# 11_-_CPU_-_JTAG_CONTROL.net
KiCad netlist of a schematic drawn in Altium Designer
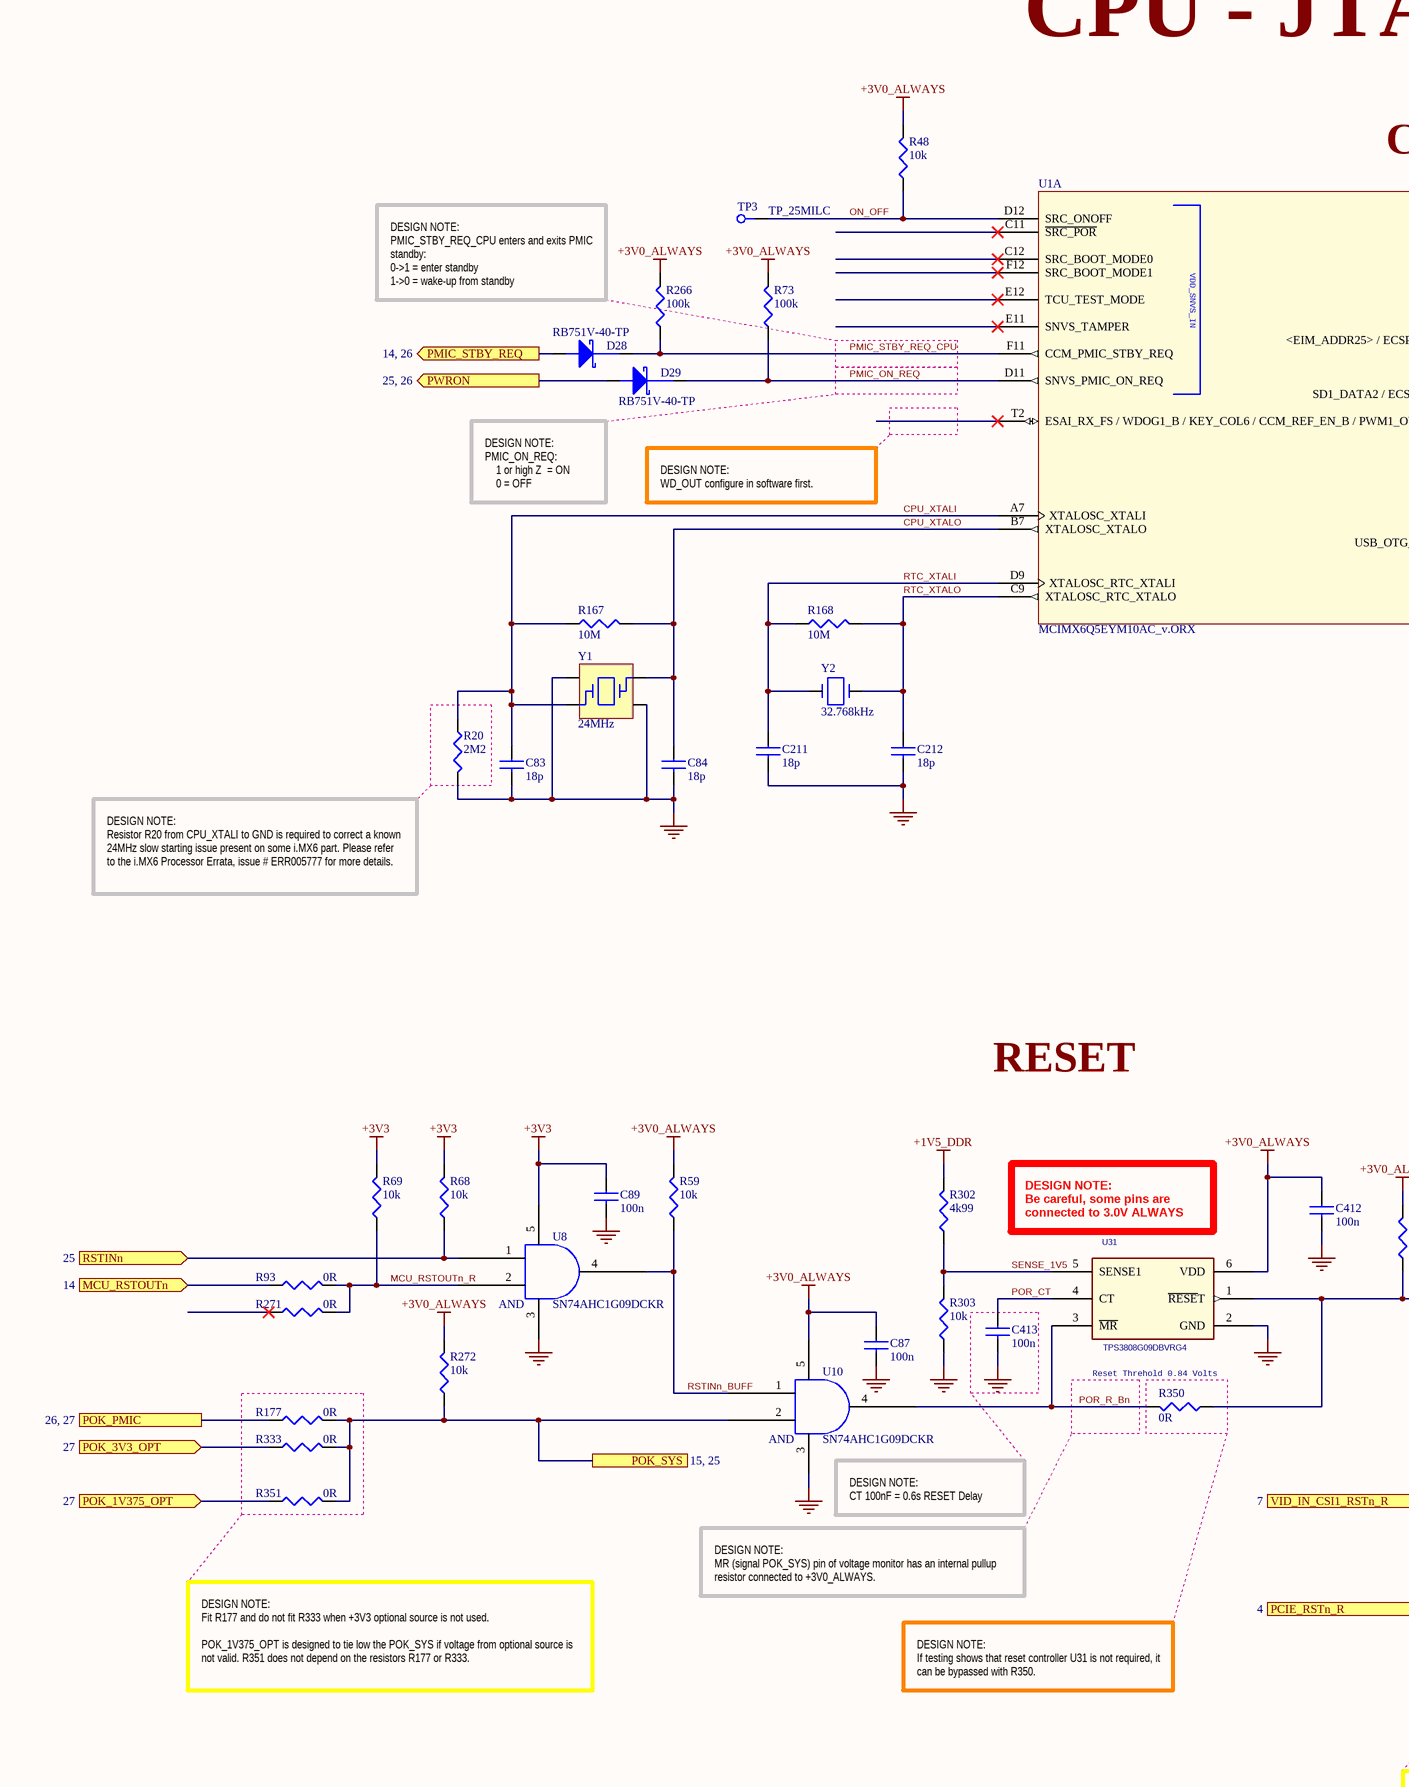
[diagram p0: [11] - CPU - JTAG, CONTROL.SchDoc, left]
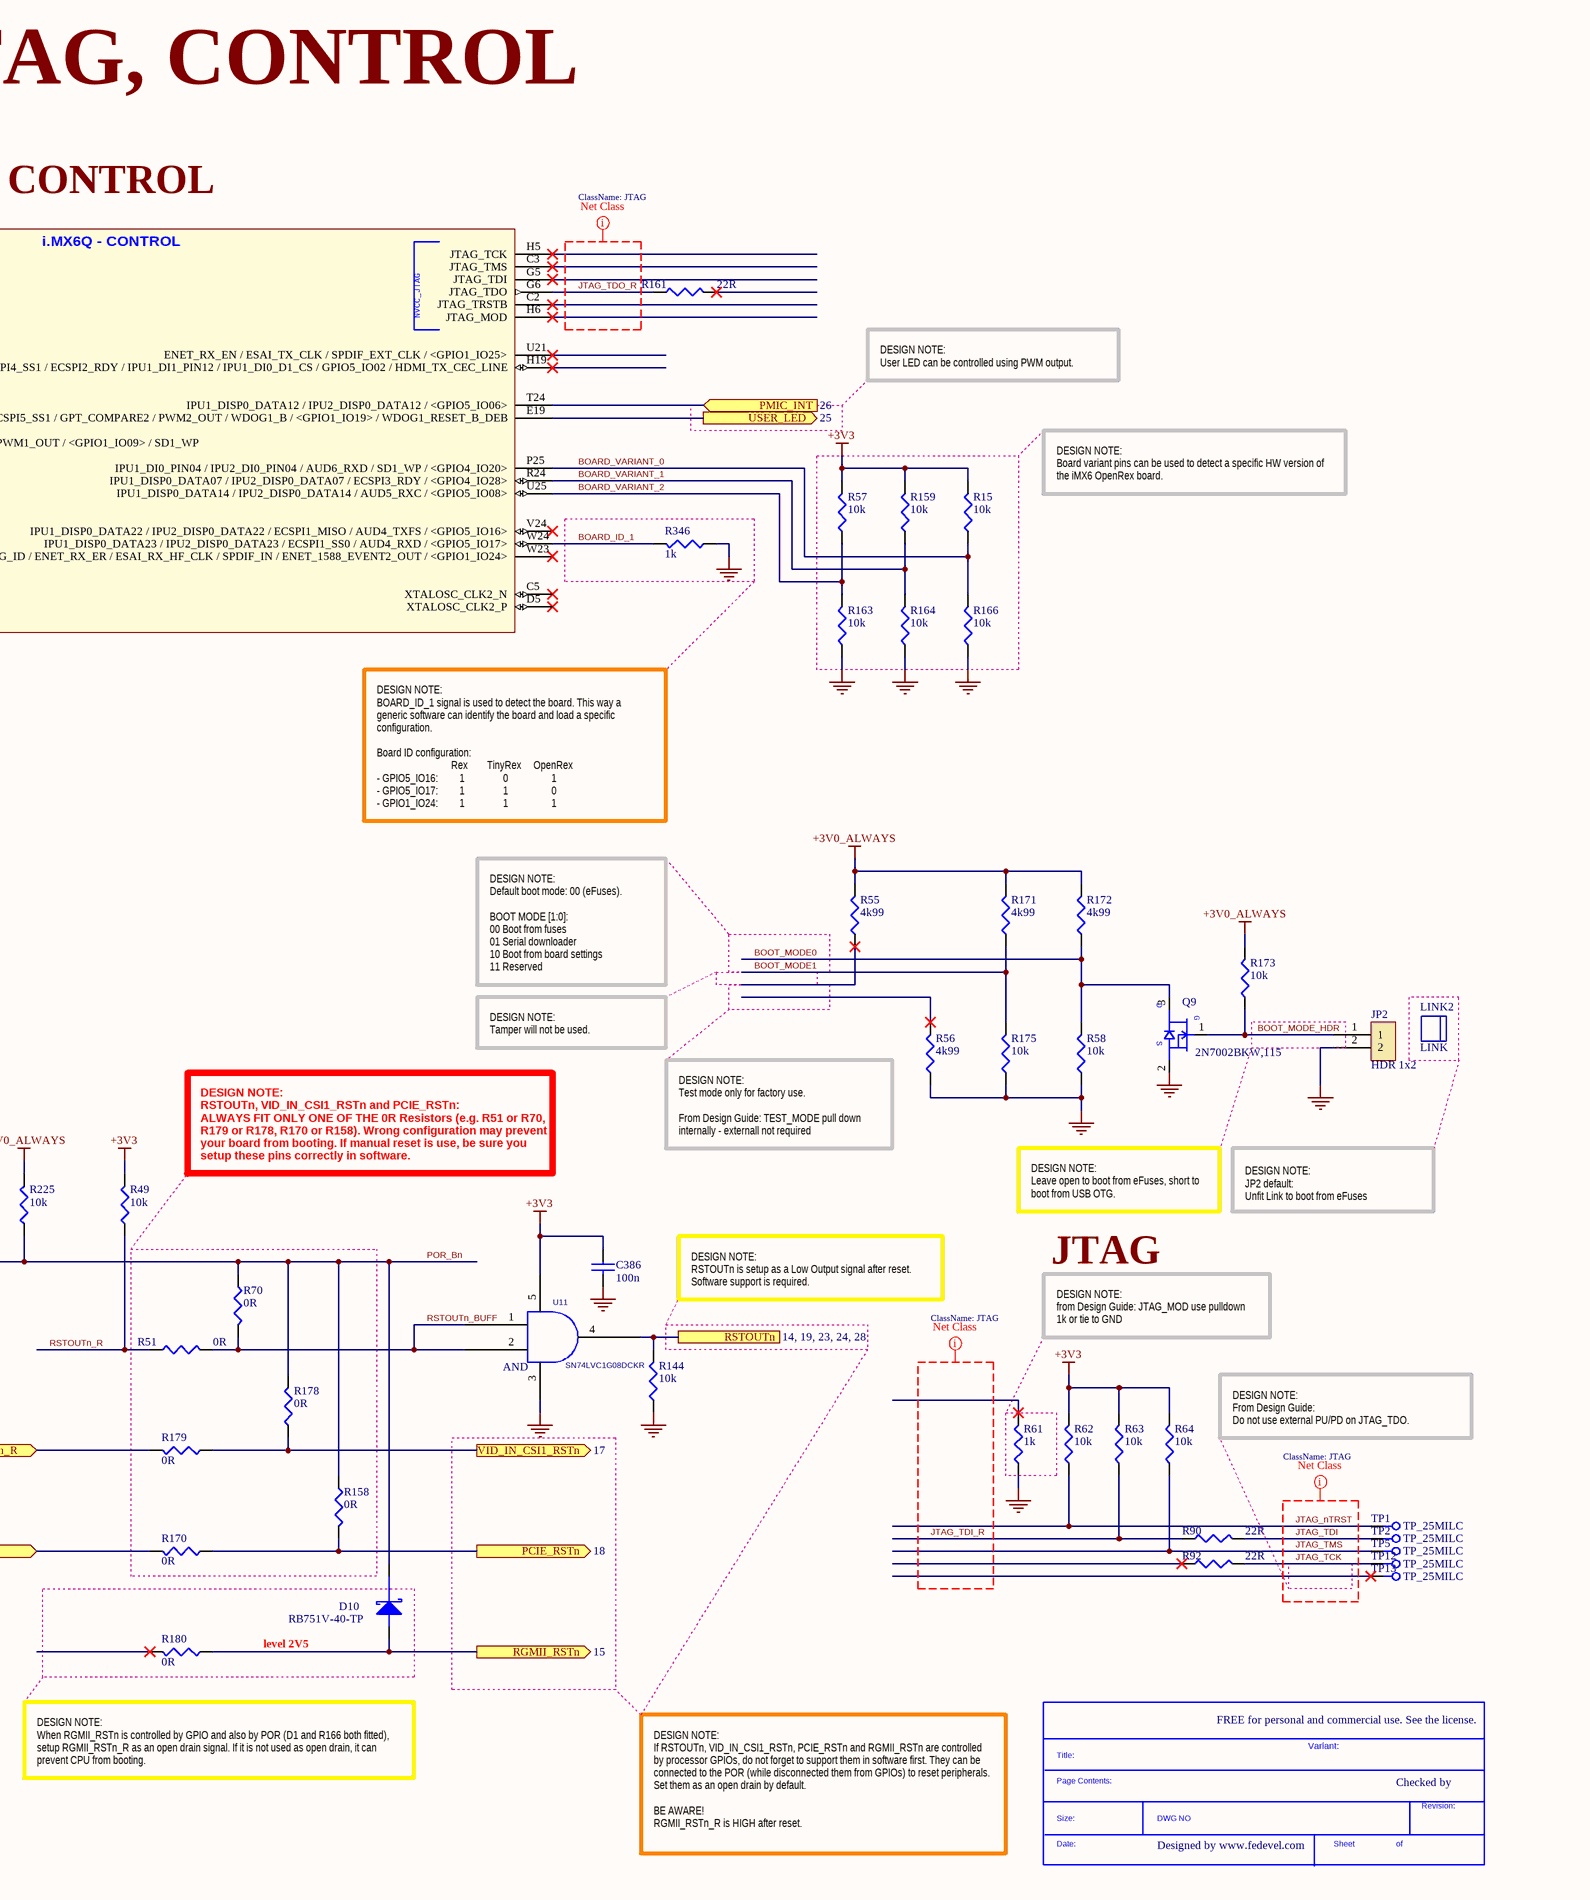
[diagram p1: [11] - CPU - JTAG, CONTROL.SchDoc, right]

(export (version "E")
  (design (tool "Eeschema 10.0.6"))
  (components
    (comp (ref "C83")
      (value "18p")
      (footprint "C0402")
      (description "CAP CER 18PF 50V C0G 5% 0402")
      (fields
        (field (name "MANUFACTURER") "TDK Corporation")
        (field (name "MANUFACTURER PART NUMBER") "C1005C0G1H180J")
      )
      (libsource (lib "Integrated_Library_FEDEVEL_APR_2015") (part "C1005C0G1H180J"))
    )
    (comp (ref "C84")
      (value "18p")
      (footprint "C0402")
      (description "CAP CER 18PF 50V C0G 5% 0402")
      (fields
        (field (name "MANUFACTURER") "TDK Corporation")
        (field (name "MANUFACTURER PART NUMBER") "C1005C0G1H180J")
      )
      (libsource (lib "Integrated_Library_FEDEVEL_APR_2015") (part "C1005C0G1H180J"))
    )
    (comp (ref "C87")
      (value "100n")
      (footprint "C0402")
      (description "CAP CER .10UF 50V X5R 10% 0402")
      (fields
        (field (name "MANUFACTURER") "TDK Corporation")
        (field (name "MANUFACTURER PART NUMBER") "C1005X5R1H104K")
      )
      (libsource (lib "Integrated_Library_FEDEVEL_APR_2015") (part "C1005X5R1H104K"))
    )
    (comp (ref "C89")
      (value "100n")
      (footprint "C0402")
      (description "CAP CER .10UF 50V X5R 10% 0402")
      (fields
        (field (name "MANUFACTURER") "TDK Corporation")
        (field (name "MANUFACTURER PART NUMBER") "C1005X5R1H104K")
      )
      (libsource (lib "Integrated_Library_FEDEVEL_APR_2015") (part "C1005X5R1H104K"))
    )
    (comp (ref "C211")
      (value "18p")
      (footprint "C0201")
      (description "CAP CER 18PF 50V 5% C0G 0201")
      (fields
        (field (name "MANUFACTURER") "TDK Corporation")
        (field (name "MANUFACTURER PART NUMBER") "C0603C0G1H180J030BA")
        (field (name ".CREATOR") "MM")
        (field (name ".CHECKED PCB") "MM")
        (field (name ".CHECKED SCH") "MM")
      )
      (libsource (lib "Integrated_Library_FEDEVEL_0201") (part "C0603C0G1H180J030BA"))
    )
    (comp (ref "C212")
      (value "18p")
      (footprint "C0201")
      (description "CAP CER 18PF 50V 5% C0G 0201")
      (fields
        (field (name "MANUFACTURER") "TDK Corporation")
        (field (name "MANUFACTURER PART NUMBER") "C0603C0G1H180J030BA")
        (field (name ".CREATOR") "MM")
        (field (name ".CHECKED PCB") "MM")
        (field (name ".CHECKED SCH") "MM")
      )
      (libsource (lib "Integrated_Library_FEDEVEL_0201") (part "C0603C0G1H180J030BA"))
    )
    (comp (ref "C386")
      (value "100n")
      (footprint "C0402")
      (description "CAP CER .10UF 50V X5R 10% 0402")
      (fields
        (field (name "MANUFACTURER") "TDK Corporation")
        (field (name "MANUFACTURER PART NUMBER") "C1005X5R1H104K")
      )
      (libsource (lib "Integrated_Library_FEDEVEL_APR_2015") (part "C1005X5R1H104K"))
    )
    (comp (ref "C412")
      (value "100n")
      (footprint "C0402")
      (description "CAP CER .10UF 50V X5R 10% 0402")
      (fields
        (field (name "MANUFACTURER") "TDK Corporation")
        (field (name "MANUFACTURER PART NUMBER") "C1005X5R1H104K")
      )
      (libsource (lib "Integrated_Library_FEDEVEL_APR_2015") (part "C1005X5R1H104K"))
    )
    (comp (ref "C413")
      (value "100n")
      (footprint "C0402")
      (description "CAP CER .10UF 50V X5R 10% 0402")
      (fields
        (field (name "MANUFACTURER") "TDK Corporation")
        (field (name "MANUFACTURER PART NUMBER") "C1005X5R1H104K")
      )
      (libsource (lib "Integrated_Library_FEDEVEL_APR_2015") (part "C1005X5R1H104K"))
    )
    (comp (ref "D10")
      (value "RB751V-40-TP")
      (footprint "SOD323")
      (description "DIODE SCHTKY 30MA 30V SOD-323")
      (fields (field (name "MANUFACTURER") "Micro Commercial Co"))
      (libsource (lib "Integrated_Library_FEDEVEL_APR_2015") (part "RB751V-40-TP"))
    )
    (comp (ref "D28")
      (value "RB751V-40-TP")
      (footprint "SOD323")
      (description "DIODE SCHTKY 30MA 30V SOD-323")
      (fields (field (name "MANUFACTURER") "Micro Commercial Co"))
      (libsource (lib "Integrated_Library_FEDEVEL_APR_2015") (part "RB751V-40-TP"))
    )
    (comp (ref "D29")
      (value "RB751V-40-TP")
      (footprint "SOD323")
      (description "DIODE SCHTKY 30MA 30V SOD-323")
      (fields (field (name "MANUFACTURER") "Micro Commercial Co"))
      (libsource (lib "Integrated_Library_FEDEVEL_APR_2015") (part "RB751V-40-TP"))
    )
    (comp (ref "JP2")
      (value "HDR 1x2")
      (footprint "HDR_1x2_2.54MM")
      (description "BERGSTIK II .100\" SR STRAIGHT")
      (fields (field (name "MANUFACTURER") "FCI") (field (name "MANUFACTURER PART NUMBER") "68001-202HLF"))
      (libsource (lib "Integrated_Library_FEDEVEL_APR_2015") (part "68001-202HLF"))
    )
    (comp (ref "LINK2")
      (value "LINK")
      (description "CONN JUMPER SHORTING .100\" GOLD")
      (fields
        (field (name "MANUFACTURER") "Sullins Connector Solutions")
        (field (name "MANUFACTURER PART NUMBER") "QPC02SXGN-RC")
      )
      (libsource (lib "Integrated_Library_FEDEVEL_APR_2015") (part "QPC02SXGN-RC"))
    )
    (comp (ref "Q9")
      (value "2N7002BKW,115")
      (footprint "SC70_SOT323")
      (description "MOSFET N-CH 60V 310MA SOT323")
      (fields (field (name "MANUFACTURER") "NXP Semiconductors"))
      (libsource (lib "Integrated_Library_FEDEVEL_APR_2015") (part "2N7002BKW,115"))
    )
    (comp (ref "R15")
      (value "10k")
      (footprint "R0402")
      (description "RES 10.0K OHM 1/16W 1% 0402 SMD")
      (fields
        (field (name "MANUFACTURER") "Yageo")
        (field (name "MANUFACTURER PART NUMBER") "RC0402FR-0710KL")
      )
      (libsource (lib "Integrated_Library_FEDEVEL_APR_2015") (part "RC0402FR-0710KL"))
    )
    (comp (ref "R20")
      (value "2M2")
      (footprint "R0402")
      (description "RES 2.20M OHM 1/16W 1% 0402 SMD")
      (fields
        (field (name "MANUFACTURER") "Vishay Dale")
        (field (name "MANUFACTURER PART NUMBER") "CRCW04022M20FKED")
        (field (name ".CREATOR") "MM")
      )
      (libsource (lib "Integrated_Library_FEDEVEL_APR_2015") (part "CRCW04022M20FKED"))
    )
    (comp (ref "R48")
      (value "10k")
      (footprint "R0402")
      (description "RES 10.0K OHM 1/16W 1% 0402 SMD")
      (fields
        (field (name "MANUFACTURER") "Yageo")
        (field (name "MANUFACTURER PART NUMBER") "RC0402FR-0710KL")
      )
      (libsource (lib "Integrated_Library_FEDEVEL_APR_2015") (part "RC0402FR-0710KL"))
    )
    (comp (ref "R49")
      (value "10k")
      (footprint "R0402")
      (description "RES 10.0K OHM 1/16W 1% 0402 SMD")
      (fields
        (field (name "MANUFACTURER") "Yageo")
        (field (name "MANUFACTURER PART NUMBER") "RC0402FR-0710KL")
      )
      (libsource (lib "Integrated_Library_FEDEVEL_APR_2015") (part "RC0402FR-0710KL"))
    )
    (comp (ref "R51")
      (value "0R")
      (footprint "R0402")
      (description "RES 0.0 OHM 1/16W 0402 SMD")
      (fields
        (field (name "MANUFACTURER") "Yageo")
        (field (name "MANUFACTURER PART NUMBER") "RC0402JR-070RL")
      )
      (libsource (lib "Integrated_Library_FEDEVEL_APR_2015") (part "RC0402JR-070RL"))
    )
    (comp (ref "R55")
      (value "4k99")
      (footprint "R0201")
      (description "RES 4.99K OHM 1/20W 1% 0201")
      (fields
        (field (name "MANUFACTURER") "Stackpole Electronics Inc")
        (field (name "MANUFACTURER PART NUMBER") "RMCF0201FT4K99")
        (field (name ".CREATOR") "MM")
        (field (name ".CHECKED PCB") "MM")
        (field (name ".CHECKED SCH") "MM")
      )
      (libsource (lib "Integrated_Library_FEDEVEL_0201") (part "RMCF0201FT4K99"))
    )
    (comp (ref "R56")
      (value "4k99")
      (footprint "R0201")
      (description "RES 4.99K OHM 1/20W 1% 0201")
      (fields
        (field (name "MANUFACTURER") "Stackpole Electronics Inc")
        (field (name "MANUFACTURER PART NUMBER") "RMCF0201FT4K99")
        (field (name ".CREATOR") "MM")
        (field (name ".CHECKED PCB") "MM")
        (field (name ".CHECKED SCH") "MM")
      )
      (libsource (lib "Integrated_Library_FEDEVEL_0201") (part "RMCF0201FT4K99"))
    )
    (comp (ref "R57")
      (value "10k")
      (footprint "R0402")
      (description "RES 10.0K OHM 1/16W 1% 0402 SMD")
      (fields
        (field (name "MANUFACTURER") "Yageo")
        (field (name "MANUFACTURER PART NUMBER") "RC0402FR-0710KL")
      )
      (libsource (lib "Integrated_Library_FEDEVEL_APR_2015") (part "RC0402FR-0710KL"))
    )
    (comp (ref "R58")
      (value "10k")
      (footprint "R0402")
      (description "RES 10.0K OHM 1/16W 1% 0402 SMD")
      (fields
        (field (name "MANUFACTURER") "Yageo")
        (field (name "MANUFACTURER PART NUMBER") "RC0402FR-0710KL")
      )
      (libsource (lib "Integrated_Library_FEDEVEL_APR_2015") (part "RC0402FR-0710KL"))
    )
    (comp (ref "R59")
      (value "10k")
      (footprint "R0402")
      (description "RES 10.0K OHM 1/16W 1% 0402 SMD")
      (fields
        (field (name "MANUFACTURER") "Yageo")
        (field (name "MANUFACTURER PART NUMBER") "RC0402FR-0710KL")
      )
      (libsource (lib "Integrated_Library_FEDEVEL_APR_2015") (part "RC0402FR-0710KL"))
    )
    (comp (ref "R61")
      (value "1k")
      (footprint "R0201")
      (description "RES 1K OHM 1/20W 1% 0201 SMD")
      (fields
        (field (name "MANUFACTURER") "Yageo")
        (field (name "MANUFACTURER PART NUMBER") "RC0201FR-071KL")
        (field (name ".CREATOR") "MM")
        (field (name ".CHECKED PCB") "MM")
        (field (name ".CHECKED SCH") "MM")
      )
      (libsource (lib "Integrated_Library_FEDEVEL_0201") (part "RC0201FR-071KL"))
    )
    (comp (ref "R62")
      (value "10k")
      (footprint "R0402")
      (description "RES 10.0K OHM 1/16W 1% 0402 SMD")
      (fields
        (field (name "MANUFACTURER") "Yageo")
        (field (name "MANUFACTURER PART NUMBER") "RC0402FR-0710KL")
      )
      (libsource (lib "Integrated_Library_FEDEVEL_APR_2015") (part "RC0402FR-0710KL"))
    )
    (comp (ref "R63")
      (value "10k")
      (footprint "R0402")
      (description "RES 10.0K OHM 1/16W 1% 0402 SMD")
      (fields
        (field (name "MANUFACTURER") "Yageo")
        (field (name "MANUFACTURER PART NUMBER") "RC0402FR-0710KL")
      )
      (libsource (lib "Integrated_Library_FEDEVEL_APR_2015") (part "RC0402FR-0710KL"))
    )
    (comp (ref "R64")
      (value "10k")
      (footprint "R0402")
      (description "RES 10.0K OHM 1/16W 1% 0402 SMD")
      (fields
        (field (name "MANUFACTURER") "Yageo")
        (field (name "MANUFACTURER PART NUMBER") "RC0402FR-0710KL")
      )
      (libsource (lib "Integrated_Library_FEDEVEL_APR_2015") (part "RC0402FR-0710KL"))
    )
    (comp (ref "R68")
      (value "10k")
      (footprint "R0402")
      (description "RES 10.0K OHM 1/16W 1% 0402 SMD")
      (fields
        (field (name "MANUFACTURER") "Yageo")
        (field (name "MANUFACTURER PART NUMBER") "RC0402FR-0710KL")
      )
      (libsource (lib "Integrated_Library_FEDEVEL_APR_2015") (part "RC0402FR-0710KL"))
    )
    (comp (ref "R69")
      (value "10k")
      (footprint "R0402")
      (description "RES 10.0K OHM 1/16W 1% 0402 SMD")
      (fields
        (field (name "MANUFACTURER") "Yageo")
        (field (name "MANUFACTURER PART NUMBER") "RC0402FR-0710KL")
      )
      (libsource (lib "Integrated_Library_FEDEVEL_APR_2015") (part "RC0402FR-0710KL"))
    )
    (comp (ref "R70")
      (value "0R")
      (footprint "R0402")
      (description "RES 0.0 OHM 1/16W 0402 SMD")
      (fields
        (field (name "MANUFACTURER") "Yageo")
        (field (name "MANUFACTURER PART NUMBER") "RC0402JR-070RL")
      )
      (libsource (lib "Integrated_Library_FEDEVEL_APR_2015") (part "RC0402JR-070RL"))
    )
    (comp (ref "R73")
      (value "100k")
      (footprint "R0402")
      (description "RES 100K OHM 1/16W 1% 0402 SMD")
      (fields
        (field (name "MANUFACTURER") "Stackpole Electronics Inc")
        (field (name "MANUFACTURER PART NUMBER") "RMCF0402FT100K")
      )
      (libsource (lib "Integrated_Library_FEDEVEL_APR_2015") (part "RMCF0402FT100K"))
    )
    (comp (ref "R90")
      (value "22R")
      (footprint "R0402")
      (description "RES 22.0 OHM 1/16W 1% 0402 SMD")
      (fields
        (field (name "MANUFACTURER") "Yageo")
        (field (name "MANUFACTURER PART NUMBER") "RC0402FR-0722RL")
      )
      (libsource (lib "Integrated_Library_FEDEVEL_APR_2015") (part "RC0402FR-0722RL"))
    )
    (comp (ref "R92")
      (value "22R")
      (footprint "R0402")
      (description "RES 22.0 OHM 1/16W 1% 0402 SMD")
      (fields
        (field (name "MANUFACTURER") "Yageo")
        (field (name "MANUFACTURER PART NUMBER") "RC0402FR-0722RL")
      )
      (libsource (lib "Integrated_Library_FEDEVEL_APR_2015") (part "RC0402FR-0722RL"))
    )
    (comp (ref "R93")
      (value "0R")
      (footprint "R0402")
      (description "RES 0.0 OHM 1/16W 0402 SMD")
      (fields
        (field (name "MANUFACTURER") "Yageo")
        (field (name "MANUFACTURER PART NUMBER") "RC0402JR-070RL")
      )
      (libsource (lib "Integrated_Library_FEDEVEL_APR_2015") (part "RC0402JR-070RL"))
    )
    (comp (ref "R144")
      (value "10k")
      (footprint "R0402")
      (description "RES 10.0K OHM 1/16W 1% 0402 SMD")
      (fields
        (field (name "MANUFACTURER") "Yageo")
        (field (name "MANUFACTURER PART NUMBER") "RC0402FR-0710KL")
      )
      (libsource (lib "Integrated_Library_FEDEVEL_APR_2015") (part "RC0402FR-0710KL"))
    )
    (comp (ref "R158")
      (value "0R")
      (footprint "R0402")
      (description "RES 0.0 OHM 1/16W 0402 SMD")
      (fields
        (field (name "MANUFACTURER") "Yageo")
        (field (name "MANUFACTURER PART NUMBER") "RC0402JR-070RL")
      )
      (libsource (lib "Integrated_Library_FEDEVEL_APR_2015") (part "RC0402JR-070RL"))
    )
    (comp (ref "R159")
      (value "10k")
      (footprint "R0402")
      (description "RES 10.0K OHM 1/16W 1% 0402 SMD")
      (fields
        (field (name "MANUFACTURER") "Yageo")
        (field (name "MANUFACTURER PART NUMBER") "RC0402FR-0710KL")
      )
      (libsource (lib "Integrated_Library_FEDEVEL_APR_2015") (part "RC0402FR-0710KL"))
    )
    (comp (ref "R161")
      (value "22R")
      (footprint "R0402")
      (description "RES 22.0 OHM 1/16W 1% 0402 SMD")
      (fields
        (field (name "MANUFACTURER") "Yageo")
        (field (name "MANUFACTURER PART NUMBER") "RC0402FR-0722RL")
      )
      (libsource (lib "Integrated_Library_FEDEVEL_APR_2015") (part "RC0402FR-0722RL"))
    )
    (comp (ref "R163")
      (value "10k")
      (footprint "R0402")
      (description "RES 10.0K OHM 1/16W 1% 0402 SMD")
      (fields
        (field (name "MANUFACTURER") "Yageo")
        (field (name "MANUFACTURER PART NUMBER") "RC0402FR-0710KL")
      )
      (libsource (lib "Integrated_Library_FEDEVEL_APR_2015") (part "RC0402FR-0710KL"))
    )
    (comp (ref "R164")
      (value "10k")
      (footprint "R0402")
      (description "RES 10.0K OHM 1/16W 1% 0402 SMD")
      (fields
        (field (name "MANUFACTURER") "Yageo")
        (field (name "MANUFACTURER PART NUMBER") "RC0402FR-0710KL")
      )
      (libsource (lib "Integrated_Library_FEDEVEL_APR_2015") (part "RC0402FR-0710KL"))
    )
    (comp (ref "R166")
      (value "10k")
      (footprint "R0402")
      (description "RES 10.0K OHM 1/16W 1% 0402 SMD")
      (fields
        (field (name "MANUFACTURER") "Yageo")
        (field (name "MANUFACTURER PART NUMBER") "RC0402FR-0710KL")
      )
      (libsource (lib "Integrated_Library_FEDEVEL_APR_2015") (part "RC0402FR-0710KL"))
    )
    (comp (ref "R167")
      (value "10M")
      (footprint "R0402")
      (description "RES 10.0M OHM 1/16W 1% 0402 SMD")
      (fields
        (field (name "MANUFACTURER") "Vishay Dale")
        (field (name "MANUFACTURER PART NUMBER") "CRCW040210M0FKED")
        (field (name ".CHECKED PCB") "RF")
        (field (name ".CHECKED SCH") "RF")
      )
      (libsource (lib "Integrated_Library_FEDEVEL_APR_2015") (part "CRCW040210M0FKED"))
    )
    (comp (ref "R168")
      (value "10M")
      (footprint "R0201")
      (description "RES 10M OHM 1/20W 1% 0201 SMD")
      (fields
        (field (name "MANUFACTURER") "Rohm Semiconductor")
        (field (name "MANUFACTURER PART NUMBER") "MCR006YZPF1005")
        (field (name ".CREATOR") "MM")
        (field (name ".CHECKED PCB") "MM")
        (field (name ".CHECKED SCH") "MM")
      )
      (libsource (lib "Integrated_Library_FEDEVEL_0201") (part "MCR006YZPF1005"))
    )
    (comp (ref "R170")
      (value "0R")
      (footprint "R0402")
      (description "RES 0.0 OHM 1/16W 0402 SMD")
      (fields
        (field (name "MANUFACTURER") "Yageo")
        (field (name "MANUFACTURER PART NUMBER") "RC0402JR-070RL")
      )
      (libsource (lib "Integrated_Library_FEDEVEL_APR_2015") (part "RC0402JR-070RL"))
    )
    (comp (ref "R171")
      (value "4k99")
      (footprint "R0402")
      (description "RES TF 4.99K OHM 1% 1/16W 0402")
      (fields
        (field (name "MANUFACTURER") "Stackpole Electronics Inc")
        (field (name "MANUFACTURER PART NUMBER") "RMCF0402FT4K99")
      )
      (libsource (lib "Integrated_Library_FEDEVEL_APR_2015") (part "RMCF0402FT4K99"))
    )
    (comp (ref "R172")
      (value "4k99")
      (footprint "R0402")
      (description "RES TF 4.99K OHM 1% 1/16W 0402")
      (fields
        (field (name "MANUFACTURER") "Stackpole Electronics Inc")
        (field (name "MANUFACTURER PART NUMBER") "RMCF0402FT4K99")
      )
      (libsource (lib "Integrated_Library_FEDEVEL_APR_2015") (part "RMCF0402FT4K99"))
    )
    (comp (ref "R173")
      (value "10k")
      (footprint "R0402")
      (description "RES 10.0K OHM 1/16W 1% 0402 SMD")
      (fields
        (field (name "MANUFACTURER") "Yageo")
        (field (name "MANUFACTURER PART NUMBER") "RC0402FR-0710KL")
      )
      (libsource (lib "Integrated_Library_FEDEVEL_APR_2015") (part "RC0402FR-0710KL"))
    )
    (comp (ref "R175")
      (value "10k")
      (footprint "R0402")
      (description "RES 10.0K OHM 1/16W 1% 0402 SMD")
      (fields
        (field (name "MANUFACTURER") "Yageo")
        (field (name "MANUFACTURER PART NUMBER") "RC0402FR-0710KL")
      )
      (libsource (lib "Integrated_Library_FEDEVEL_APR_2015") (part "RC0402FR-0710KL"))
    )
    (comp (ref "R177")
      (value "0R")
      (footprint "R0402")
      (description "RES 0.0 OHM 1/16W 0402 SMD")
      (fields
        (field (name "MANUFACTURER") "Yageo")
        (field (name "MANUFACTURER PART NUMBER") "RC0402JR-070RL")
      )
      (libsource (lib "Integrated_Library_FEDEVEL_APR_2015") (part "RC0402JR-070RL"))
    )
    (comp (ref "R178")
      (value "0R")
      (footprint "R0402")
      (description "RES 0.0 OHM 1/16W 0402 SMD")
      (fields
        (field (name "MANUFACTURER") "Yageo")
        (field (name "MANUFACTURER PART NUMBER") "RC0402JR-070RL")
      )
      (libsource (lib "Integrated_Library_FEDEVEL_APR_2015") (part "RC0402JR-070RL"))
    )
    (comp (ref "R179")
      (value "0R")
      (footprint "R0402")
      (description "RES 0.0 OHM 1/16W 0402 SMD")
      (fields
        (field (name "MANUFACTURER") "Yageo")
        (field (name "MANUFACTURER PART NUMBER") "RC0402JR-070RL")
      )
      (libsource (lib "Integrated_Library_FEDEVEL_APR_2015") (part "RC0402JR-070RL"))
    )
    (comp (ref "R180")
      (value "0R")
      (footprint "R0402")
      (description "RES 0.0 OHM 1/16W 0402 SMD")
      (fields
        (field (name "MANUFACTURER") "Yageo")
        (field (name "MANUFACTURER PART NUMBER") "RC0402JR-070RL")
      )
      (libsource (lib "Integrated_Library_FEDEVEL_APR_2015") (part "RC0402JR-070RL"))
    )
    (comp (ref "R225")
      (value "10k")
      (footprint "R0402")
      (description "RES 10.0K OHM 1/16W 1% 0402 SMD")
      (fields
        (field (name "MANUFACTURER") "Yageo")
        (field (name "MANUFACTURER PART NUMBER") "RC0402FR-0710KL")
      )
      (libsource (lib "Integrated_Library_FEDEVEL_APR_2015") (part "RC0402FR-0710KL"))
    )
    (comp (ref "R266")
      (value "100k")
      (footprint "R0402")
      (description "RES 100K OHM 1/16W 1% 0402 SMD")
      (fields
        (field (name "MANUFACTURER") "Stackpole Electronics Inc")
        (field (name "MANUFACTURER PART NUMBER") "RMCF0402FT100K")
      )
      (libsource (lib "Integrated_Library_FEDEVEL_APR_2015") (part "RMCF0402FT100K"))
    )
    (comp (ref "R271")
      (value "0R")
      (footprint "R0402")
      (description "RES 0.0 OHM 1/16W 0402 SMD")
      (fields
        (field (name "MANUFACTURER") "Yageo")
        (field (name "MANUFACTURER PART NUMBER") "RC0402JR-070RL")
      )
      (libsource (lib "Integrated_Library_FEDEVEL_APR_2015") (part "RC0402JR-070RL"))
    )
    (comp (ref "R272")
      (value "10k")
      (footprint "R0402")
      (description "RES 10.0K OHM 1/16W 1% 0402 SMD")
      (fields
        (field (name "MANUFACTURER") "Yageo")
        (field (name "MANUFACTURER PART NUMBER") "RC0402FR-0710KL")
      )
      (libsource (lib "Integrated_Library_FEDEVEL_APR_2015") (part "RC0402FR-0710KL"))
    )
    (comp (ref "R302")
      (value "4k99")
      (footprint "R0402")
      (description "RES TF 4.99K OHM 1% 1/16W 0402")
      (fields
        (field (name "MANUFACTURER") "Stackpole Electronics Inc")
        (field (name "MANUFACTURER PART NUMBER") "RMCF0402FT4K99")
      )
      (libsource (lib "Integrated_Library_FEDEVEL_APR_2015") (part "RMCF0402FT4K99"))
    )
    (comp (ref "R303")
      (value "10k")
      (footprint "R0402")
      (description "RES 10.0K OHM 1/16W 1% 0402 SMD")
      (fields
        (field (name "MANUFACTURER") "Yageo")
        (field (name "MANUFACTURER PART NUMBER") "RC0402FR-0710KL")
      )
      (libsource (lib "Integrated_Library_FEDEVEL_APR_2015") (part "RC0402FR-0710KL"))
    )
    (comp (ref "R333")
      (value "0R")
      (footprint "R0402")
      (description "RES 0.0 OHM 1/16W 0402 SMD")
      (fields
        (field (name "MANUFACTURER") "Yageo")
        (field (name "MANUFACTURER PART NUMBER") "RC0402JR-070RL")
      )
      (libsource (lib "Integrated_Library_FEDEVEL_APR_2015") (part "RC0402JR-070RL"))
    )
    (comp (ref "R346")
      (value "1k")
      (footprint "R0402")
      (description "RES 1.00K OHM 1/16W 1% 0402 SMD")
      (fields
        (field (name "MANUFACTURER") "Yageo")
        (field (name "MANUFACTURER PART NUMBER") "RC0402FR-071KL")
      )
      (libsource (lib "Integrated_Library_FEDEVEL_APR_2015") (part "RC0402FR-071KL"))
    )
    (comp (ref "R350")
      (value "0R")
      (footprint "R0402")
      (description "RES 0.0 OHM 1/16W 0402 SMD")
      (fields
        (field (name "MANUFACTURER") "Yageo")
        (field (name "MANUFACTURER PART NUMBER") "RC0402JR-070RL")
      )
      (libsource (lib "Integrated_Library_FEDEVEL_APR_2015") (part "RC0402JR-070RL"))
    )
    (comp (ref "R351")
      (value "0R")
      (footprint "R0402")
      (description "RES 0.0 OHM 1/16W 0402 SMD")
      (fields
        (field (name "MANUFACTURER") "Yageo")
        (field (name "MANUFACTURER PART NUMBER") "RC0402JR-070RL")
      )
      (libsource (lib "Integrated_Library_FEDEVEL_APR_2015") (part "RC0402JR-070RL"))
    )
    (comp (ref "TP1")
      (value "TP_25MILC")
      (footprint "TP_25C")
      (description "Test Point 25mil")
      (libsource (lib "Integrated_Library_FEDEVEL_APR_2015") (part "TP_25MILC"))
    )
    (comp (ref "TP2")
      (value "TP_25MILC")
      (footprint "TP_25C")
      (description "Test Point 25mil")
      (libsource (lib "Integrated_Library_FEDEVEL_APR_2015") (part "TP_25MILC"))
    )
    (comp (ref "TP3")
      (value "TP_25MILC")
      (footprint "TP_25C")
      (description "Test Point 25mil")
      (libsource (lib "Integrated_Library_FEDEVEL_APR_2015") (part "TP_25MILC"))
    )
    (comp (ref "TP5")
      (value "TP_25MILC")
      (footprint "TP_25C")
      (description "Test Point 25mil")
      (libsource (lib "Integrated_Library_FEDEVEL_APR_2015") (part "TP_25MILC"))
    )
    (comp (ref "TP12")
      (value "TP_25MILC")
      (footprint "TP_25C")
      (description "Test Point 25mil")
      (libsource (lib "Integrated_Library_FEDEVEL_APR_2015") (part "TP_25MILC"))
    )
    (comp (ref "TP13")
      (value "TP_25MILC")
      (footprint "TP_25C")
      (description "Test Point 25mil")
      (libsource (lib "Integrated_Library_FEDEVEL_APR_2015") (part "TP_25MILC"))
    )
    (comp (ref "U1")
      (value "MCIMX6Q5EYM10AC_v.ORX")
      (footprint "PBGA624")
      (description "IC MCU 32BIT ARM QUAD 624FCBGA")
      (fields
        (field (name "MANUFACTURER") "Freescale Semiconductor")
        (field (name "MANUFACTURER PART NUMBER") "MCIMX6Q5EYM10AC")
        (field (name ".CREATOR") "MM")
        (field (name ".CHECKED PCB") "MM, checked by RF")
      )
      (libsource (lib "Integrated_Library_FEDEVEL_APR_2015") (part "MCIMX6Q5EYM10AC_v.ORX"))
    )
    (comp (ref "U8")
      (value "SN74AHC1G09DCKR")
      (footprint "SC70_5")
      (description "IC GATE AND 1CH 2-INP SC-70-5")
      (fields
        (field (name "MANUFACTURER") "Texas Instruments")
        (field (name ".CREATOR") "MM")
        (field (name ".CHECKED SCH") "MM")
        (field (name ".CHECKED PCB") "RF, used by MM")
      )
      (libsource (lib "Integrated_Library_FEDEVEL_APR_2015") (part "SN74AHC1G09DCKR"))
    )
    (comp (ref "U10")
      (value "SN74AHC1G09DCKR")
      (footprint "SC70_5")
      (description "IC GATE AND 1CH 2-INP SC-70-5")
      (fields
        (field (name "MANUFACTURER") "Texas Instruments")
        (field (name ".CREATOR") "MM")
        (field (name ".CHECKED SCH") "MM")
        (field (name ".CHECKED PCB") "RF, used by MM")
      )
      (libsource (lib "Integrated_Library_FEDEVEL_APR_2015") (part "SN74AHC1G09DCKR"))
    )
    (comp (ref "U11")
      (value "SN74LVC1G08DCKR")
      (footprint "SC70_5")
      (description "SINGLE POSITIVE AND GATE SC-70")
      (fields (field (name "MANUFACTURER") "Texas Instruments"))
      (libsource (lib "Integrated_Library_FEDEVEL_APR_2015") (part "SN74LVC1G08DCKR"))
    )
    (comp (ref "U31")
      (value "TPS3808G09DBVRG4")
      (footprint "DBV_SOT_23_6")
      (description "IC VOLT SUPERVISOR 0.9V SOT23-6")
      (fields (field (name "PART #") "102020-0009R") (field (name "MANUFACTURER") "Texas Instruments"))
      (libsource (lib "Integrated_Library_FEDEVEL_APR_2015") (part "TPS3808G09DBVR"))
    )
    (comp (ref "Y1")
      (value "24MHz")
      (footprint "ABM8")
      (description "CRYSTAL 24MHZ 18PF SMD")
      (fields
        (field (name "MANUFACTURER") "Abracon Corporation")
        (field (name "MANUFACTURER PART NUMBER") "ABM8-24.000MHZ-R60-D-1-W-T")
        (field (name ".CREATOR") "MM")
        (field (name ".CHECKED PCB") "MM")
        (field (name ".CHECKED SCH") "MM")
      )
      (libsource (lib "Integrated_Library_FEDEVEL_APR_2015") (part "ABM8-24.000MHZ-R60-D-1-W-T"))
    )
    (comp (ref "Y2")
      (value "32.768kHz")
      (footprint "ABS06")
      (description "CRYSTAL 32.768 KHZ 9.0 PF SMD")
      (fields
        (field (name "MANUFACTURER") "Abracon Corporation")
        (field (name "MANUFACTURER PART NUMBER") "ABS06-32.768KHZ-9-1-T")
      )
      (libsource (lib "Integrated_Library_FEDEVEL_APR_2015") (part "ABS06-32.768KHZ-9-1-T"))
    )
  )
  (nets
    (net (code "1") (name "+1V5_DDR") (class "Default")
      (node (ref "R302") (pin "2") (pinfunction "2_2") (pintype "passive"))
    )
    (net (code "2") (name "+3V0_ALWAYS") (class "Default")
      (node (ref "C412") (pin "1") (pinfunction "1_1") (pintype "passive"))
      (node (ref "C87") (pin "1") (pinfunction "1_1") (pintype "passive"))
      (node (ref "R171") (pin "2") (pinfunction "2_2") (pintype "passive"))
      (node (ref "R172") (pin "2") (pinfunction "2_2") (pintype "passive"))
      (node (ref "R173") (pin "2") (pinfunction "2_2") (pintype "passive"))
      (node (ref "R225") (pin "2") (pinfunction "2_2") (pintype "passive"))
      (node (ref "R266") (pin "2") (pinfunction "2_2") (pintype "passive"))
      (node (ref "R272") (pin "2") (pinfunction "2_2") (pintype "passive"))
      (node (ref "R48") (pin "2") (pinfunction "2_2") (pintype "passive"))
      (node (ref "R55") (pin "2") (pinfunction "2_2") (pintype "passive"))
      (node (ref "R59") (pin "2") (pinfunction "2_2") (pintype "passive"))
      (node (ref "R73") (pin "2") (pinfunction "2_2") (pintype "passive"))
      (node (ref "U10") (pin "5") (pinfunction "VCC_5") (pintype "power_in"))
      (node (ref "U31") (pin "6") (pinfunction "VDD_6") (pintype "passive"))
    )
    (net (code "3") (name "+3V3") (class "Default")
      (node (ref "C386") (pin "1") (pinfunction "1_1") (pintype "passive"))
      (node (ref "C89") (pin "1") (pinfunction "1_1") (pintype "passive"))
      (node (ref "R15") (pin "2") (pinfunction "2_2") (pintype "passive"))
      (node (ref "R159") (pin "2") (pinfunction "2_2") (pintype "passive"))
      (node (ref "R49") (pin "2") (pinfunction "2_2") (pintype "passive"))
      (node (ref "R57") (pin "2") (pinfunction "2_2") (pintype "passive"))
      (node (ref "R62") (pin "2") (pinfunction "2_2") (pintype "passive"))
      (node (ref "R63") (pin "2") (pinfunction "2_2") (pintype "passive"))
      (node (ref "R64") (pin "2") (pinfunction "2_2") (pintype "passive"))
      (node (ref "R68") (pin "2") (pinfunction "2_2") (pintype "passive"))
      (node (ref "R69") (pin "2") (pinfunction "2_2") (pintype "passive"))
      (node (ref "U11") (pin "5") (pinfunction "VCC_5") (pintype "power_in"))
      (node (ref "U8") (pin "5") (pinfunction "VCC_5") (pintype "power_in"))
    )
    (net (code "4") (name "/BOARD_ID_1") (class "Default")
      (node (ref "R346") (pin "2") (pinfunction "2_2") (pintype "passive"))
      (node (ref "U1") (pin "W24") (pinfunction "IPU1_DISP0_DATA23_/_IPU2_DISP0_DATA23_/_ECSPI1_SS0_/_AUD4_RXD_/_<GPIO5_IO17>_W24") (pintype "bidirectional"))
    )
    (net (code "5") (name "/BOARD_VARIANT_0") (class "Default")
      (node (ref "R15") (pin "1") (pinfunction "1_1") (pintype "passive"))
      (node (ref "R166") (pin "2") (pinfunction "2_2") (pintype "passive"))
      (node (ref "U1") (pin "P25") (pinfunction "IPU1_DI0_PIN04_/_IPU2_DI0_PIN04_/_AUD6_RXD_/_SD1_WP_/_<GPIO4_IO20>_P25") (pintype "passive"))
    )
    (net (code "6") (name "/BOARD_VARIANT_1") (class "Default")
      (node (ref "R159") (pin "1") (pinfunction "1_1") (pintype "passive"))
      (node (ref "R164") (pin "2") (pinfunction "2_2") (pintype "passive"))
      (node (ref "U1") (pin "R24") (pinfunction "IPU1_DISP0_DATA07_/_IPU2_DISP0_DATA07_/_ECSPI3_RDY_/_<GPIO4_IO28>_R24") (pintype "bidirectional"))
    )
    (net (code "7") (name "/BOARD_VARIANT_2") (class "Default")
      (node (ref "R163") (pin "2") (pinfunction "2_2") (pintype "passive"))
      (node (ref "R57") (pin "1") (pinfunction "1_1") (pintype "passive"))
      (node (ref "U1") (pin "U25") (pinfunction "IPU1_DISP0_DATA14_/_IPU2_DISP0_DATA14_/_AUD5_RXC_/_<GPIO5_IO08>_U25") (pintype "bidirectional"))
    )
    (net (code "8") (name "/BOOT_MODE0") (class "Default")
      (node (ref "Q9") (pin "3") (pinfunction "DRAIN_3") (pintype "passive"))
      (node (ref "R172") (pin "1") (pinfunction "1_1") (pintype "passive"))
      (node (ref "R58") (pin "2") (pinfunction "2_2") (pintype "passive"))
    )
    (net (code "9") (name "/BOOT_MODE1") (class "Default")
      (node (ref "R171") (pin "1") (pinfunction "1_1") (pintype "passive"))
      (node (ref "R175") (pin "2") (pinfunction "2_2") (pintype "passive"))
    )
    (net (code "10") (name "/BOOT_MODE_HDR") (class "Default")
      (node (ref "JP2") (pin "1") (pinfunction "1_1") (pintype "passive"))
      (node (ref "Q9") (pin "1") (pinfunction "GATE_1") (pintype "passive"))
      (node (ref "R173") (pin "1") (pinfunction "1_1") (pintype "passive"))
    )
    (net (code "11") (name "/CPU_XTALI") (class "Default")
      (node (ref "C83") (pin "1") (pinfunction "1_1") (pintype "passive"))
      (node (ref "R167") (pin "1") (pinfunction "1_1") (pintype "passive"))
      (node (ref "R20") (pin "1") (pinfunction "1_1") (pintype "passive"))
      (node (ref "U1") (pin "A7") (pinfunction "XTALOSC_XTALI_A7") (pintype "passive"))
      (node (ref "Y1") (pin "3") (pinfunction "3_3") (pintype "passive"))
    )
    (net (code "12") (name "/CPU_XTALO") (class "Default")
      (node (ref "C84") (pin "1") (pinfunction "1_1") (pintype "passive"))
      (node (ref "R167") (pin "2") (pinfunction "2_2") (pintype "passive"))
      (node (ref "U1") (pin "B7") (pinfunction "XTALOSC_XTALO_B7") (pintype "output"))
      (node (ref "Y1") (pin "1") (pinfunction "1_1") (pintype "passive"))
    )
    (net (code "13") (name "/JTAG_TCK") (class "Default")
      (node (ref "R92") (pin "2") (pinfunction "2_2") (pintype "passive"))
      (node (ref "TP12") (pin "1") (pinfunction "1_1") (pintype "passive"))
    )
    (net (code "14") (name "/JTAG_TDI") (class "Default")
      (node (ref "R90") (pin "2") (pinfunction "2_2") (pintype "passive"))
      (node (ref "TP2") (pin "1") (pinfunction "1_1") (pintype "passive"))
    )
    (net (code "15") (name "/JTAG_TDI_R") (class "Default")
      (node (ref "R63") (pin "1") (pinfunction "1_1") (pintype "passive"))
      (node (ref "R90") (pin "1") (pinfunction "1_1") (pintype "passive"))
    )
    (net (code "16") (name "/JTAG_TDO_R") (class "Default")
      (node (ref "R161") (pin "1") (pinfunction "1_1") (pintype "passive"))
      (node (ref "U1") (pin "G6") (pinfunction "JTAG_TDO_G6") (pintype "output"))
    )
    (net (code "17") (name "/JTAG_TMS") (class "Default")
      (node (ref "R64") (pin "1") (pinfunction "1_1") (pintype "passive"))
      (node (ref "TP5") (pin "1") (pinfunction "1_1") (pintype "passive"))
    )
    (net (code "18") (name "/JTAG_nTRST") (class "Default")
      (node (ref "R62") (pin "1") (pinfunction "1_1") (pintype "passive"))
      (node (ref "TP1") (pin "1") (pinfunction "1_1") (pintype "passive"))
    )
    (net (code "19") (name "/MCU_RSTOUTn") (class "Default")
      (node (ref "R93") (pin "1") (pinfunction "1_1") (pintype "passive"))
    )
    (net (code "20") (name "/MCU_RSTOUTn_R") (class "Default")
      (node (ref "R271") (pin "2") (pinfunction "2_2") (pintype "passive"))
      (node (ref "R69") (pin "1") (pinfunction "1_1") (pintype "passive"))
      (node (ref "R93") (pin "2") (pinfunction "2_2") (pintype "passive"))
      (node (ref "U8") (pin "2") (pinfunction "B_2") (pintype "passive"))
    )
    (net (code "21") (name "/ON_OFF") (class "Default")
      (node (ref "R48") (pin "1") (pinfunction "1_1") (pintype "passive"))
      (node (ref "TP3") (pin "1") (pinfunction "1_1") (pintype "passive"))
      (node (ref "U1") (pin "D12") (pinfunction "SRC_ONOFF_D12") (pintype "passive"))
    )
    (net (code "22") (name "/PCIE_RSTn") (class "Default")
      (node (ref "R158") (pin "2") (pinfunction "2_2") (pintype "passive"))
      (node (ref "R170") (pin "1") (pinfunction "1_1") (pintype "passive"))
    )
    (net (code "23") (name "/PCIE_RSTn_R") (class "Default")
      (node (ref "R170") (pin "2") (pinfunction "2_2") (pintype "passive"))
    )
    (net (code "24") (name "/PMIC_INT") (class "Default")
      (node (ref "U1") (pin "T24") (pinfunction "IPU1_DISP0_DATA12_/_IPU2_DISP0_DATA12_/_<GPIO5_IO06>_T24") (pintype "passive"))
    )
    (net (code "25") (name "/PMIC_ON_REQ") (class "Default")
      (node (ref "D29") (pin "1") (pinfunction "cathode_1") (pintype "passive"))
      (node (ref "R73") (pin "1") (pinfunction "1_1") (pintype "passive"))
      (node (ref "U1") (pin "D11") (pinfunction "SNVS_PMIC_ON_REQ_D11") (pintype "output"))
    )
    (net (code "26") (name "/PMIC_STBY_REQ") (class "Default")
      (node (ref "D28") (pin "2") (pinfunction "ANODE_2") (pintype "passive"))
    )
    (net (code "27") (name "/PMIC_STBY_REQ_CPU") (class "Default")
      (node (ref "D28") (pin "1") (pinfunction "cathode_1") (pintype "passive"))
      (node (ref "R266") (pin "1") (pinfunction "1_1") (pintype "passive"))
      (node (ref "U1") (pin "F11") (pinfunction "CCM_PMIC_STBY_REQ_F11") (pintype "output"))
    )
    (net (code "28") (name "/POK_1V375_OPT") (class "Default")
      (node (ref "R351") (pin "1") (pinfunction "1_1") (pintype "passive"))
    )
    (net (code "29") (name "/POK_3V3_OPT") (class "Default")
      (node (ref "R333") (pin "1") (pinfunction "1_1") (pintype "passive"))
    )
    (net (code "30") (name "/POK_PMIC") (class "Default")
      (node (ref "R177") (pin "1") (pinfunction "1_1") (pintype "passive"))
    )
    (net (code "31") (name "/POK_SYS") (class "Default")
      (node (ref "R177") (pin "2") (pinfunction "2_2") (pintype "passive"))
      (node (ref "R272") (pin "1") (pinfunction "1_1") (pintype "passive"))
      (node (ref "R333") (pin "2") (pinfunction "2_2") (pintype "passive"))
      (node (ref "R351") (pin "2") (pinfunction "2_2") (pintype "passive"))
      (node (ref "U10") (pin "2") (pinfunction "B_2") (pintype "passive"))
    )
    (net (code "32") (name "/POR_Bn") (class "Default")
      (node (ref "D10") (pin "1") (pinfunction "cathode_1") (pintype "passive"))
      (node (ref "R158") (pin "1") (pinfunction "1_1") (pintype "passive"))
      (node (ref "R178") (pin "2") (pinfunction "2_2") (pintype "passive"))
      (node (ref "R225") (pin "1") (pinfunction "1_1") (pintype "passive"))
      (node (ref "R350") (pin "1") (pinfunction "1_1") (pintype "passive"))
      (node (ref "R70") (pin "1") (pinfunction "1_1") (pintype "passive"))
      (node (ref "U31") (pin "1") (pinfunction "~{RESE}T_1") (pintype "output"))
    )
    (net (code "33") (name "/POR_CT") (class "Default")
      (node (ref "C413") (pin "1") (pinfunction "1_1") (pintype "passive"))
      (node (ref "U31") (pin "4") (pinfunction "CT_4") (pintype "passive"))
    )
    (net (code "34") (name "/POR_R_Bn") (class "Default")
      (node (ref "R350") (pin "2") (pinfunction "2_2") (pintype "passive"))
      (node (ref "U10") (pin "4") (pinfunction "Y_4") (pintype "passive"))
      (node (ref "U31") (pin "3") (pinfunction "~{MR}_3") (pintype "passive"))
    )
    (net (code "35") (name "/PWRON") (class "Default")
      (node (ref "D29") (pin "2") (pinfunction "ANODE_2") (pintype "passive"))
    )
    (net (code "36") (name "/RGMII_RSTn") (class "Default")
      (node (ref "D10") (pin "2") (pinfunction "ANODE_2") (pintype "passive"))
      (node (ref "R180") (pin "1") (pinfunction "1_1") (pintype "passive"))
    )
    (net (code "37") (name "/RSTINn") (class "Default")
      (node (ref "R68") (pin "1") (pinfunction "1_1") (pintype "passive"))
      (node (ref "U8") (pin "1") (pinfunction "A_1") (pintype "passive"))
    )
    (net (code "38") (name "/RSTINn_BUFF") (class "Default")
      (node (ref "R59") (pin "1") (pinfunction "1_1") (pintype "passive"))
      (node (ref "U10") (pin "1") (pinfunction "A_1") (pintype "passive"))
      (node (ref "U8") (pin "4") (pinfunction "Y_4") (pintype "passive"))
    )
    (net (code "39") (name "/RSTOUTn") (class "Default")
      (node (ref "R144") (pin "2") (pinfunction "2_2") (pintype "passive"))
      (node (ref "U11") (pin "4") (pinfunction "Y_4") (pintype "passive"))
    )
    (net (code "40") (name "/RSTOUTn_BUFF") (class "Default")
      (node (ref "R51") (pin "2") (pinfunction "2_2") (pintype "passive"))
      (node (ref "R70") (pin "2") (pinfunction "2_2") (pintype "passive"))
      (node (ref "U11") (pin "1") (pinfunction "A_1") (pintype "passive"))
      (node (ref "U11") (pin "2") (pinfunction "B_2") (pintype "passive"))
    )
    (net (code "41") (name "/RSTOUTn_R") (class "Default")
      (node (ref "R49") (pin "1") (pinfunction "1_1") (pintype "passive"))
      (node (ref "R51") (pin "1") (pinfunction "1_1") (pintype "passive"))
    )
    (net (code "42") (name "/RTC_XTALI") (class "Default")
      (node (ref "C211") (pin "1") (pinfunction "1_1") (pintype "passive"))
      (node (ref "R168") (pin "1") (pinfunction "1_1") (pintype "passive"))
      (node (ref "U1") (pin "D9") (pinfunction "XTALOSC_RTC_XTALI_D9") (pintype "passive"))
      (node (ref "Y2") (pin "1") (pinfunction "1_1") (pintype "passive"))
    )
    (net (code "43") (name "/RTC_XTALO") (class "Default")
      (node (ref "C212") (pin "1") (pinfunction "1_1") (pintype "passive"))
      (node (ref "R168") (pin "2") (pinfunction "2_2") (pintype "passive"))
      (node (ref "U1") (pin "C9") (pinfunction "XTALOSC_RTC_XTALO_C9") (pintype "output"))
      (node (ref "Y2") (pin "2") (pinfunction "2_2") (pintype "passive"))
    )
    (net (code "44") (name "/SENSE_1V5") (class "Default")
      (node (ref "R302") (pin "1") (pinfunction "1_1") (pintype "passive"))
      (node (ref "R303") (pin "2") (pinfunction "2_2") (pintype "passive"))
      (node (ref "U31") (pin "5") (pinfunction "SENSE1_5") (pintype "passive"))
    )
    (net (code "45") (name "/USER_LED") (class "Default")
      (node (ref "U1") (pin "E19") (pinfunction "SD1_DATA2_/_ECSPI5_SS1_/_GPT_COMPARE2_/_PWM2_OUT_/_WDOG1_B_/_<GPIO1_IO19>_/_WDOG1_RESET_B_DEB_E19") (pintype "passive"))
    )
    (net (code "46") (name "/VID_IN_CSI1_RSTn") (class "Default")
      (node (ref "R178") (pin "1") (pinfunction "1_1") (pintype "passive"))
      (node (ref "R179") (pin "1") (pinfunction "1_1") (pintype "passive"))
    )
    (net (code "47") (name "/VID_IN_CSI1_RSTn_R") (class "Default")
      (node (ref "R179") (pin "2") (pinfunction "2_2") (pintype "passive"))
    )
    (net (code "48") (name "GND") (class "Default")
      (node (ref "C211") (pin "2") (pinfunction "2_2") (pintype "passive"))
      (node (ref "C212") (pin "2") (pinfunction "2_2") (pintype "passive"))
      (node (ref "C386") (pin "2") (pinfunction "2_2") (pintype "passive"))
      (node (ref "C412") (pin "2") (pinfunction "2_2") (pintype "passive"))
      (node (ref "C413") (pin "2") (pinfunction "2_2") (pintype "passive"))
      (node (ref "C83") (pin "2") (pinfunction "2_2") (pintype "passive"))
      (node (ref "C84") (pin "2") (pinfunction "2_2") (pintype "passive"))
      (node (ref "C87") (pin "2") (pinfunction "2_2") (pintype "passive"))
      (node (ref "C89") (pin "2") (pinfunction "2_2") (pintype "passive"))
      (node (ref "JP2") (pin "2") (pinfunction "2_2") (pintype "passive"))
      (node (ref "Q9") (pin "2") (pinfunction "SOURCE_2") (pintype "passive"))
      (node (ref "R144") (pin "1") (pinfunction "1_1") (pintype "passive"))
      (node (ref "R163") (pin "1") (pinfunction "1_1") (pintype "passive"))
      (node (ref "R164") (pin "1") (pinfunction "1_1") (pintype "passive"))
      (node (ref "R166") (pin "1") (pinfunction "1_1") (pintype "passive"))
      (node (ref "R175") (pin "1") (pinfunction "1_1") (pintype "passive"))
      (node (ref "R20") (pin "2") (pinfunction "2_2") (pintype "passive"))
      (node (ref "R303") (pin "1") (pinfunction "1_1") (pintype "passive"))
      (node (ref "R346") (pin "1") (pinfunction "1_1") (pintype "passive"))
      (node (ref "R56") (pin "1") (pinfunction "1_1") (pintype "passive"))
      (node (ref "R58") (pin "1") (pinfunction "1_1") (pintype "passive"))
      (node (ref "R61") (pin "1") (pinfunction "1_1") (pintype "passive"))
      (node (ref "U10") (pin "3") (pinfunction "GND_3") (pintype "power_in"))
      (node (ref "U11") (pin "3") (pinfunction "GND_3") (pintype "power_in"))
      (node (ref "U31") (pin "2") (pinfunction "GND_2") (pintype "passive"))
      (node (ref "U8") (pin "3") (pinfunction "GND_3") (pintype "power_in"))
      (node (ref "Y1") (pin "2") (pinfunction "2_2") (pintype "passive"))
      (node (ref "Y1") (pin "4") (pinfunction "4_4") (pintype "passive"))
    )
    (net (code "49") (name "unconnected-(R55-Pad1)") (class "Default")
      (node (ref "R55") (pin "1") (pinfunction "1_1") (pintype "passive+no_connect"))
    )
    (net (code "50") (name "unconnected-(R56-Pad2)") (class "Default")
      (node (ref "R56") (pin "2") (pinfunction "2_2") (pintype "passive+no_connect"))
    )
    (net (code "51") (name "unconnected-(R61-Pad2)") (class "Default")
      (node (ref "R61") (pin "2") (pinfunction "2_2") (pintype "passive+no_connect"))
    )
    (net (code "52") (name "unconnected-(R92-Pad1)") (class "Default")
      (node (ref "R92") (pin "1") (pinfunction "1_1") (pintype "passive+no_connect"))
    )
    (net (code "53") (name "unconnected-(R161-Pad2)") (class "Default")
      (node (ref "R161") (pin "2") (pinfunction "2_2") (pintype "passive+no_connect"))
    )
    (net (code "54") (name "unconnected-(R180-Pad2)") (class "Default")
      (node (ref "R180") (pin "2") (pinfunction "2_2") (pintype "passive+no_connect"))
    )
    (net (code "55") (name "unconnected-(R271-Pad1)") (class "Default")
      (node (ref "R271") (pin "1") (pinfunction "1_1") (pintype "passive+no_connect"))
    )
    (net (code "56") (name "unconnected-(TP13-Pad1)") (class "Default")
      (node (ref "TP13") (pin "1") (pinfunction "1_1") (pintype "passive+no_connect"))
    )
    (net (code "57") (name "unconnected-(U1A-<EIM_ADDR25>_{slash}_ECSPI4_SS1_{slash}_ECSPI2_RDY_{slash}_IPU1_DI1_PIN12_{slash}_IPU1_DI0_D1_CS_{slash}_GPIO5_IO02_{slash}_HDMI_TX_CEC_LINE-PadH19)") (class "Default")
      (node (ref "U1") (pin "H19") (pinfunction "<EIM_ADDR25>_/_ECSPI4_SS1_/_ECSPI2_RDY_/_IPU1_DI1_PIN12_/_IPU1_DI0_D1_CS_/_GPIO5_IO02_/_HDMI_TX_CEC_LINE_H19") (pintype "bidirectional+no_connect"))
    )
    (net (code "58") (name "unconnected-(U1A-ENET_RX_EN_{slash}_ESAI_TX_CLK_{slash}_SPDIF_EXT_CLK_{slash}_<GPIO1_IO25>-PadU21)") (class "Default")
      (node (ref "U1") (pin "U21") (pinfunction "ENET_RX_EN_/_ESAI_TX_CLK_/_SPDIF_EXT_CLK_/_<GPIO1_IO25>_U21") (pintype "passive+no_connect"))
    )
    (net (code "59") (name "unconnected-(U1A-ESAI_RX_FS_{slash}_WDOG1_B_{slash}_KEY_COL6_{slash}_CCM_REF_EN_B_{slash}_PWM1_OUT_{slash}_<GPIO1_IO09>_{slash}_SD1_WP-PadT2)") (class "Default")
      (node (ref "U1") (pin "T2") (pinfunction "ESAI_RX_FS_/_WDOG1_B_/_KEY_COL6_/_CCM_REF_EN_B_/_PWM1_OUT_/_<GPIO1_IO09>_/_SD1_WP_T2") (pintype "bidirectional+no_connect"))
    )
    (net (code "60") (name "unconnected-(U1A-IPU1_DISP0_DATA22_{slash}_IPU2_DISP0_DATA22_{slash}_ECSPI1_MISO_{slash}_AUD4_TXFS_{slash}_<GPIO5_IO16>-PadV24)") (class "Default")
      (node (ref "U1") (pin "V24") (pinfunction "IPU1_DISP0_DATA22_/_IPU2_DISP0_DATA22_/_ECSPI1_MISO_/_AUD4_TXFS_/_<GPIO5_IO16>_V24") (pintype "bidirectional+no_connect"))
    )
    (net (code "61") (name "unconnected-(U1A-JTAG_MOD-PadH6)") (class "Default")
      (node (ref "U1") (pin "H6") (pinfunction "JTAG_MOD_H6") (pintype "passive+no_connect"))
    )
    (net (code "62") (name "unconnected-(U1A-JTAG_TCK-PadH5)") (class "Default")
      (node (ref "U1") (pin "H5") (pinfunction "JTAG_TCK_H5") (pintype "passive+no_connect"))
    )
    (net (code "63") (name "unconnected-(U1A-JTAG_TDI-PadG5)") (class "Default")
      (node (ref "U1") (pin "G5") (pinfunction "JTAG_TDI_G5") (pintype "passive+no_connect"))
    )
    (net (code "64") (name "unconnected-(U1A-JTAG_TMS-PadC3)") (class "Default")
      (node (ref "U1") (pin "C3") (pinfunction "JTAG_TMS_C3") (pintype "passive+no_connect"))
    )
    (net (code "65") (name "unconnected-(U1A-JTAG_TRSTB-PadC2)") (class "Default")
      (node (ref "U1") (pin "C2") (pinfunction "JTAG_TRSTB_C2") (pintype "passive+no_connect"))
    )
    (net (code "66") (name "unconnected-(U1A-SNVS_TAMPER-PadE11)") (class "Default")
      (node (ref "U1") (pin "E11") (pinfunction "SNVS_TAMPER_E11") (pintype "passive+no_connect"))
    )
    (net (code "67") (name "unconnected-(U1A-SRC_BOOT_MODE0-PadC12)") (class "Default")
      (node (ref "U1") (pin "C12") (pinfunction "SRC_BOOT_MODE0_C12") (pintype "passive+no_connect"))
    )
    (net (code "68") (name "unconnected-(U1A-SRC_BOOT_MODE1-PadF12)") (class "Default")
      (node (ref "U1") (pin "F12") (pinfunction "SRC_BOOT_MODE1_F12") (pintype "passive+no_connect"))
    )
    (net (code "69") (name "unconnected-(U1A-TCU_TEST_MODE-PadE12)") (class "Default")
      (node (ref "U1") (pin "E12") (pinfunction "TCU_TEST_MODE_E12") (pintype "passive+no_connect"))
    )
    (net (code "70") (name "unconnected-(U1A-USB_OTG_ID_{slash}_ENET_RX_ER_{slash}_ESAI_RX_HF_CLK_{slash}_SPDIF_IN_{slash}_ENET_1588_EVENT2_OUT_{slash}_<GPIO1_IO24>-PadW23)") (class "Default")
      (node (ref "U1") (pin "W23") (pinfunction "USB_OTG_ID_/_ENET_RX_ER_/_ESAI_RX_HF_CLK_/_SPDIF_IN_/_ENET_1588_EVENT2_OUT_/_<GPIO1_IO24>_W23") (pintype "passive+no_connect"))
    )
    (net (code "71") (name "unconnected-(U1A-XTALOSC_CLK2_N-PadC5)") (class "Default")
      (node (ref "U1") (pin "C5") (pinfunction "XTALOSC_CLK2_N_C5") (pintype "bidirectional+no_connect"))
    )
    (net (code "72") (name "unconnected-(U1A-XTALOSC_CLK2_P-PadD5)") (class "Default")
      (node (ref "U1") (pin "D5") (pinfunction "XTALOSC_CLK2_P_D5") (pintype "bidirectional+no_connect"))
    )
    (net (code "73") (name "unconnected-(U1A-~{SRC_POR}-PadC11)") (class "Default")
      (node (ref "U1") (pin "C11") (pinfunction "~{SRC_POR}_C11") (pintype "passive+no_connect"))
    )
  )
)
